# dub_siren_board.net
KiCad netlist of a schematic drawn in EasyEDA Pro
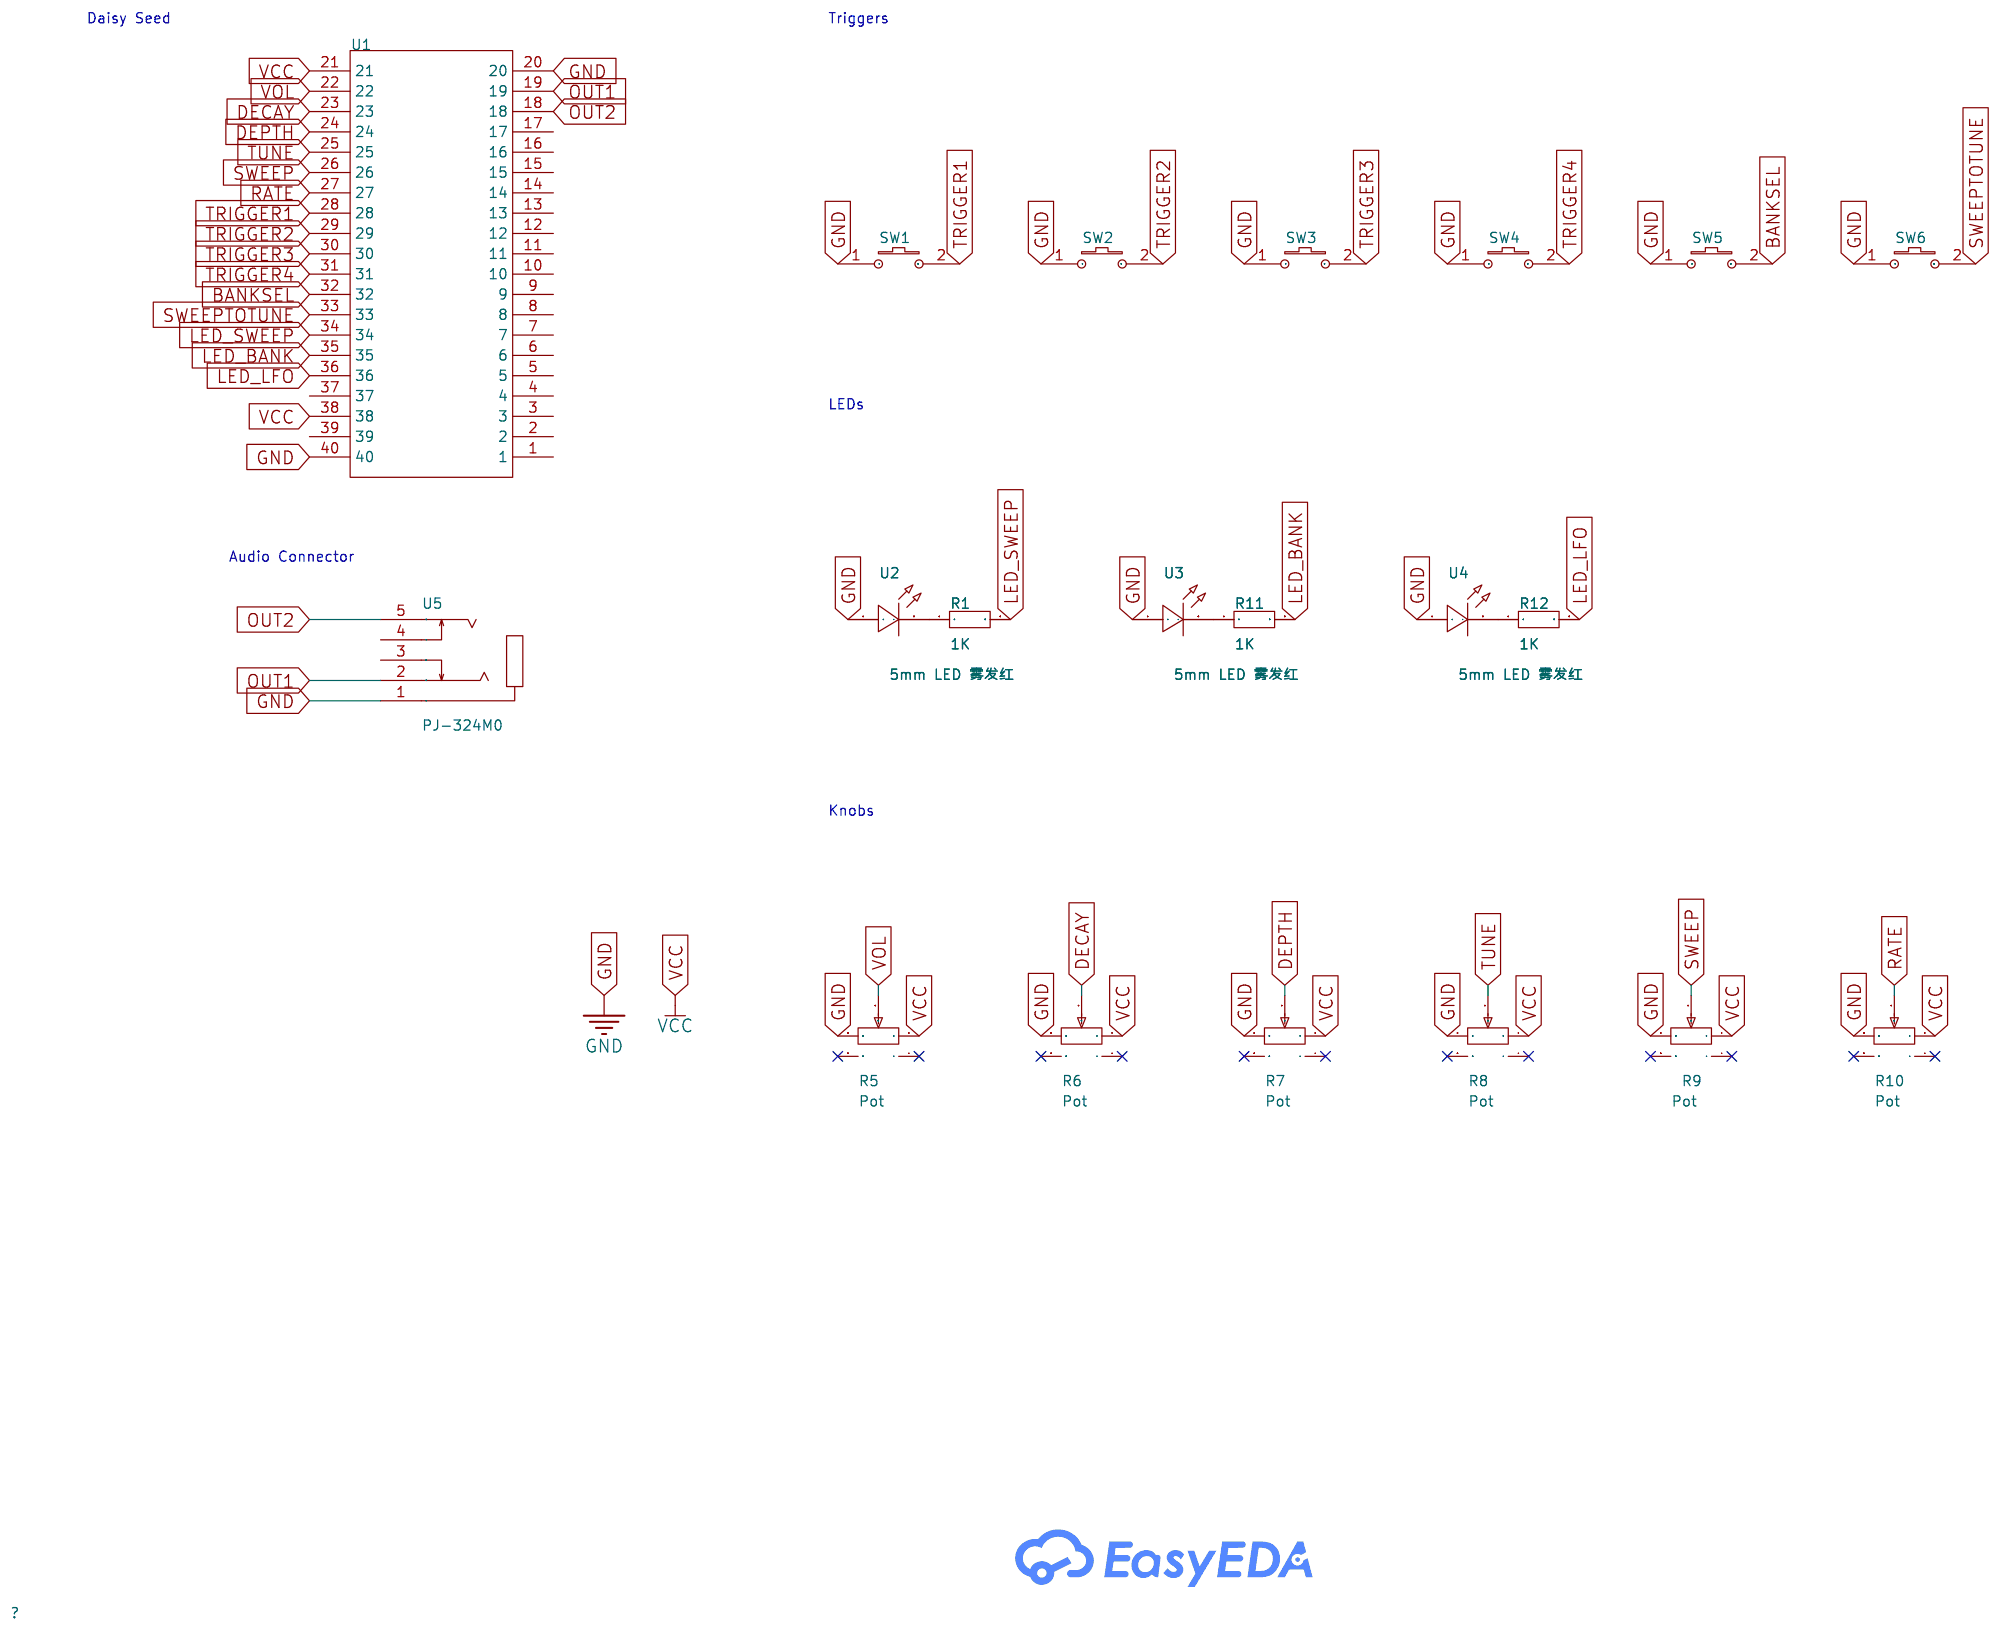
[diagram p0: schematic sheet]

(export (version "E")
  (design (tool "Eeschema 10.0.6"))
  (components
    (comp (ref "R1") (value "1K") (footprint "easyedapro:R0603") (libsource (lib "easyedapro") (part "Res")))
    (comp (ref "R5")
      (value "Pot")
      (footprint "easyedapro:RES-ADJ-TH_RV09")
      (libsource (lib "easyedapro") (part "RV09AF-40-15K-B10K-0C"))
    )
    (comp (ref "R6")
      (value "Pot")
      (footprint "easyedapro:RES-ADJ-TH_RV09")
      (libsource (lib "easyedapro") (part "RV09AF-40-15K-B10K-0C"))
    )
    (comp (ref "R7")
      (value "Pot")
      (footprint "easyedapro:RES-ADJ-TH_RV09")
      (libsource (lib "easyedapro") (part "RV09AF-40-15K-B10K-0C"))
    )
    (comp (ref "R8")
      (value "Pot")
      (footprint "easyedapro:RES-ADJ-TH_RV09")
      (libsource (lib "easyedapro") (part "RV09AF-40-15K-B10K-0C"))
    )
    (comp (ref "R9")
      (value "Pot")
      (footprint "easyedapro:RES-ADJ-TH_RV09")
      (libsource (lib "easyedapro") (part "RV09AF-40-15K-B10K-0C"))
    )
    (comp (ref "R10")
      (value "Pot")
      (footprint "easyedapro:RES-ADJ-TH_RV09")
      (libsource (lib "easyedapro") (part "RV09AF-40-15K-B10K-0C"))
    )
    (comp (ref "R11") (value "1K") (footprint "easyedapro:R0603") (libsource (lib "easyedapro") (part "Res")))
    (comp (ref "R12") (value "1K") (footprint "easyedapro:R0603") (libsource (lib "easyedapro") (part "Res")))
    (comp (ref "SW1")
      (value "~")
      (footprint "easyedapro:SWITCH CHERRY MX")
      (fields (field (name "Manufacturer Part") "MX1A-11NW") (field (name "Manufacturer") "ZF"))
      (libsource (lib "easyedapro") (part "Switch Cherry MX"))
    )
    (comp (ref "SW2")
      (value "~")
      (footprint "easyedapro:SWITCH CHERRY MX")
      (fields (field (name "Manufacturer Part") "MX1A-11NW") (field (name "Manufacturer") "ZF"))
      (libsource (lib "easyedapro") (part "Switch Cherry MX"))
    )
    (comp (ref "SW3")
      (value "~")
      (footprint "easyedapro:SWITCH CHERRY MX")
      (fields (field (name "Manufacturer Part") "MX1A-11NW") (field (name "Manufacturer") "ZF"))
      (libsource (lib "easyedapro") (part "Switch Cherry MX"))
    )
    (comp (ref "SW4")
      (value "~")
      (footprint "easyedapro:SWITCH CHERRY MX")
      (fields (field (name "Manufacturer Part") "MX1A-11NW") (field (name "Manufacturer") "ZF"))
      (libsource (lib "easyedapro") (part "Switch Cherry MX"))
    )
    (comp (ref "SW5")
      (value "~")
      (footprint "easyedapro:SWITCH CHERRY MX")
      (fields (field (name "Manufacturer Part") "MX1A-11NW") (field (name "Manufacturer") "ZF"))
      (libsource (lib "easyedapro") (part "Switch Cherry MX"))
    )
    (comp (ref "SW6")
      (value "~")
      (footprint "easyedapro:SWITCH CHERRY MX")
      (fields (field (name "Manufacturer Part") "MX1A-11NW") (field (name "Manufacturer") "ZF"))
      (libsource (lib "easyedapro") (part "Switch Cherry MX"))
    )
    (comp (ref "U1")
      (value "~")
      (footprint "easyedapro:40 PinSocket")
      (libsource (lib "easyedapro") (part "40 PinSocket"))
    )
    (comp (ref "U2")
      (value "5mm LED 雾发红")
      (footprint "easyedapro:LED-TH_BD5.0-P2.54-FD")
      (libsource (lib "easyedapro") (part "5MM LED 雾发红"))
    )
    (comp (ref "U3")
      (value "5mm LED 雾发红")
      (footprint "easyedapro:LED-TH_BD5.0-P2.54-FD")
      (libsource (lib "easyedapro") (part "5MM LED 雾发红"))
    )
    (comp (ref "U4")
      (value "5mm LED 雾发红")
      (footprint "easyedapro:LED-TH_BD5.0-P2.54-FD")
      (libsource (lib "easyedapro") (part "5MM LED 雾发红"))
    )
    (comp (ref "U5")
      (value "PJ-324M0")
      (footprint "easyedapro:AUDIO-TH_PJ-324-M")
      (fields (field (name "Manufacturer") "XKB Connection(中国星坤)"))
      (libsource (lib "easyedapro") (part "PJ-324M0"))
    )
  )
  (nets
    (net (code "1") (name "BANKSEL") (class "Default")
      (node (ref "SW5") (pin "2") (pinfunction "2_2") (pintype "input"))
      (node (ref "U1") (pin "32") (pinfunction "32_32") (pintype "input"))
    )
    (net (code "2") (name "DECAY") (class "Default")
      (node (ref "R6") (pin "2") (pinfunction "2_2") (pintype "input"))
      (node (ref "U1") (pin "23") (pinfunction "23_23") (pintype "input"))
    )
    (net (code "3") (name "DEPTH") (class "Default")
      (node (ref "R7") (pin "2") (pinfunction "2_2") (pintype "input"))
      (node (ref "U1") (pin "24") (pinfunction "24_24") (pintype "input"))
    )
    (net (code "4") (name "GND") (class "Default")
      (node (ref "R10") (pin "3") (pinfunction "3_3") (pintype "input"))
      (node (ref "R5") (pin "3") (pinfunction "3_3") (pintype "input"))
      (node (ref "R6") (pin "3") (pinfunction "3_3") (pintype "input"))
      (node (ref "R7") (pin "3") (pinfunction "3_3") (pintype "input"))
      (node (ref "R8") (pin "3") (pinfunction "3_3") (pintype "input"))
      (node (ref "R9") (pin "3") (pinfunction "3_3") (pintype "input"))
      (node (ref "SW1") (pin "1") (pinfunction "1_1") (pintype "input"))
      (node (ref "SW2") (pin "1") (pinfunction "1_1") (pintype "input"))
      (node (ref "SW3") (pin "1") (pinfunction "1_1") (pintype "input"))
      (node (ref "SW4") (pin "1") (pinfunction "1_1") (pintype "input"))
      (node (ref "SW5") (pin "1") (pinfunction "1_1") (pintype "input"))
      (node (ref "SW6") (pin "1") (pinfunction "1_1") (pintype "input"))
      (node (ref "U1") (pin "20") (pinfunction "20_20") (pintype "input"))
      (node (ref "U1") (pin "40") (pinfunction "40_40") (pintype "input"))
      (node (ref "U2") (pin "1") (pinfunction "+_1") (pintype "unspecified"))
      (node (ref "U3") (pin "1") (pinfunction "+_1") (pintype "unspecified"))
      (node (ref "U4") (pin "1") (pinfunction "+_1") (pintype "unspecified"))
      (node (ref "U5") (pin "1") (pinfunction "1_1") (pintype "unspecified"))
    )
    (net (code "5") (name "LED_BANK") (class "Default")
      (node (ref "R11") (pin "2") (pinfunction "2_2") (pintype "input"))
      (node (ref "U1") (pin "35") (pinfunction "35_35") (pintype "input"))
    )
    (net (code "6") (name "LED_LFO") (class "Default")
      (node (ref "R12") (pin "2") (pinfunction "2_2") (pintype "input"))
      (node (ref "U1") (pin "36") (pinfunction "36_36") (pintype "input"))
    )
    (net (code "7") (name "LED_SWEEP") (class "Default")
      (node (ref "R1") (pin "2") (pinfunction "2_2") (pintype "input"))
      (node (ref "U1") (pin "34") (pinfunction "34_34") (pintype "input"))
    )
    (net (code "8") (name "Net-(U2--)") (class "Default")
      (node (ref "R1") (pin "1") (pinfunction "1_1") (pintype "input"))
      (node (ref "U2") (pin "2") (pinfunction "-_2") (pintype "unspecified"))
    )
    (net (code "9") (name "Net-(U3--)") (class "Default")
      (node (ref "R11") (pin "1") (pinfunction "1_1") (pintype "input"))
      (node (ref "U3") (pin "2") (pinfunction "-_2") (pintype "unspecified"))
    )
    (net (code "10") (name "Net-(U4--)") (class "Default")
      (node (ref "R12") (pin "1") (pinfunction "1_1") (pintype "input"))
      (node (ref "U4") (pin "2") (pinfunction "-_2") (pintype "unspecified"))
    )
    (net (code "11") (name "OUT1") (class "Default")
      (node (ref "U1") (pin "19") (pinfunction "19_19") (pintype "input"))
      (node (ref "U5") (pin "2") (pinfunction "2_2") (pintype "unspecified"))
    )
    (net (code "12") (name "OUT2") (class "Default")
      (node (ref "U1") (pin "18") (pinfunction "18_18") (pintype "input"))
      (node (ref "U5") (pin "5") (pinfunction "5_5") (pintype "unspecified"))
    )
    (net (code "13") (name "RATE") (class "Default")
      (node (ref "R10") (pin "2") (pinfunction "2_2") (pintype "input"))
      (node (ref "U1") (pin "27") (pinfunction "27_27") (pintype "input"))
    )
    (net (code "14") (name "SWEEP") (class "Default")
      (node (ref "R9") (pin "2") (pinfunction "2_2") (pintype "input"))
      (node (ref "U1") (pin "26") (pinfunction "26_26") (pintype "input"))
    )
    (net (code "15") (name "SWEEPTOTUNE") (class "Default")
      (node (ref "SW6") (pin "2") (pinfunction "2_2") (pintype "input"))
      (node (ref "U1") (pin "33") (pinfunction "33_33") (pintype "input"))
    )
    (net (code "16") (name "TRIGGER1") (class "Default")
      (node (ref "SW1") (pin "2") (pinfunction "2_2") (pintype "input"))
      (node (ref "U1") (pin "28") (pinfunction "28_28") (pintype "input"))
    )
    (net (code "17") (name "TRIGGER2") (class "Default")
      (node (ref "SW2") (pin "2") (pinfunction "2_2") (pintype "input"))
      (node (ref "U1") (pin "29") (pinfunction "29_29") (pintype "input"))
    )
    (net (code "18") (name "TRIGGER3") (class "Default")
      (node (ref "SW3") (pin "2") (pinfunction "2_2") (pintype "input"))
      (node (ref "U1") (pin "30") (pinfunction "30_30") (pintype "input"))
    )
    (net (code "19") (name "TRIGGER4") (class "Default")
      (node (ref "SW4") (pin "2") (pinfunction "2_2") (pintype "input"))
      (node (ref "U1") (pin "31") (pinfunction "31_31") (pintype "input"))
    )
    (net (code "20") (name "TUNE") (class "Default")
      (node (ref "R8") (pin "2") (pinfunction "2_2") (pintype "input"))
      (node (ref "U1") (pin "25") (pinfunction "25_25") (pintype "input"))
    )
    (net (code "21") (name "VCC") (class "Default")
      (node (ref "R10") (pin "1") (pinfunction "1_1") (pintype "input"))
      (node (ref "R5") (pin "1") (pinfunction "1_1") (pintype "input"))
      (node (ref "R6") (pin "1") (pinfunction "1_1") (pintype "input"))
      (node (ref "R7") (pin "1") (pinfunction "1_1") (pintype "input"))
      (node (ref "R8") (pin "1") (pinfunction "1_1") (pintype "input"))
      (node (ref "R9") (pin "1") (pinfunction "1_1") (pintype "input"))
      (node (ref "U1") (pin "21") (pinfunction "21_21") (pintype "input"))
      (node (ref "U1") (pin "38") (pinfunction "38_38") (pintype "input"))
    )
    (net (code "22") (name "VOL") (class "Default")
      (node (ref "R5") (pin "2") (pinfunction "2_2") (pintype "input"))
      (node (ref "U1") (pin "22") (pinfunction "22_22") (pintype "input"))
    )
    (net (code "23") (name "unconnected-(R5-Pad4)") (class "Default")
      (node (ref "R5") (pin "4") (pinfunction "4_4") (pintype "input+no_connect"))
    )
    (net (code "24") (name "unconnected-(R5-Pad5)") (class "Default")
      (node (ref "R5") (pin "5") (pinfunction "5_5") (pintype "input+no_connect"))
    )
    (net (code "25") (name "unconnected-(R6-Pad4)") (class "Default")
      (node (ref "R6") (pin "4") (pinfunction "4_4") (pintype "input+no_connect"))
    )
    (net (code "26") (name "unconnected-(R6-Pad5)") (class "Default")
      (node (ref "R6") (pin "5") (pinfunction "5_5") (pintype "input+no_connect"))
    )
    (net (code "27") (name "unconnected-(R7-Pad4)") (class "Default")
      (node (ref "R7") (pin "4") (pinfunction "4_4") (pintype "input+no_connect"))
    )
    (net (code "28") (name "unconnected-(R7-Pad5)") (class "Default")
      (node (ref "R7") (pin "5") (pinfunction "5_5") (pintype "input+no_connect"))
    )
    (net (code "29") (name "unconnected-(R8-Pad4)") (class "Default")
      (node (ref "R8") (pin "4") (pinfunction "4_4") (pintype "input+no_connect"))
    )
    (net (code "30") (name "unconnected-(R8-Pad5)") (class "Default")
      (node (ref "R8") (pin "5") (pinfunction "5_5") (pintype "input+no_connect"))
    )
    (net (code "31") (name "unconnected-(R9-Pad4)") (class "Default")
      (node (ref "R9") (pin "4") (pinfunction "4_4") (pintype "input+no_connect"))
    )
    (net (code "32") (name "unconnected-(R9-Pad5)") (class "Default")
      (node (ref "R9") (pin "5") (pinfunction "5_5") (pintype "input+no_connect"))
    )
    (net (code "33") (name "unconnected-(R10-Pad4)") (class "Default")
      (node (ref "R10") (pin "4") (pinfunction "4_4") (pintype "input+no_connect"))
    )
    (net (code "34") (name "unconnected-(R10-Pad5)") (class "Default")
      (node (ref "R10") (pin "5") (pinfunction "5_5") (pintype "input+no_connect"))
    )
    (net (code "35") (name "unconnected-(U1-Pad1)") (class "Default")
      (node (ref "U1") (pin "1") (pinfunction "1_1") (pintype "input"))
    )
    (net (code "36") (name "unconnected-(U1-Pad2)") (class "Default")
      (node (ref "U1") (pin "2") (pinfunction "2_2") (pintype "input"))
    )
    (net (code "37") (name "unconnected-(U1-Pad3)") (class "Default")
      (node (ref "U1") (pin "3") (pinfunction "3_3") (pintype "input"))
    )
    (net (code "38") (name "unconnected-(U1-Pad4)") (class "Default")
      (node (ref "U1") (pin "4") (pinfunction "4_4") (pintype "input"))
    )
    (net (code "39") (name "unconnected-(U1-Pad5)") (class "Default")
      (node (ref "U1") (pin "5") (pinfunction "5_5") (pintype "input"))
    )
    (net (code "40") (name "unconnected-(U1-Pad6)") (class "Default")
      (node (ref "U1") (pin "6") (pinfunction "6_6") (pintype "input"))
    )
    (net (code "41") (name "unconnected-(U1-Pad7)") (class "Default")
      (node (ref "U1") (pin "7") (pinfunction "7_7") (pintype "input"))
    )
    (net (code "42") (name "unconnected-(U1-Pad8)") (class "Default")
      (node (ref "U1") (pin "8") (pinfunction "8_8") (pintype "input"))
    )
    (net (code "43") (name "unconnected-(U1-Pad9)") (class "Default")
      (node (ref "U1") (pin "9") (pinfunction "9_9") (pintype "input"))
    )
    (net (code "44") (name "unconnected-(U1-Pad10)") (class "Default")
      (node (ref "U1") (pin "10") (pinfunction "10_10") (pintype "input"))
    )
    (net (code "45") (name "unconnected-(U1-Pad11)") (class "Default")
      (node (ref "U1") (pin "11") (pinfunction "11_11") (pintype "input"))
    )
    (net (code "46") (name "unconnected-(U1-Pad12)") (class "Default")
      (node (ref "U1") (pin "12") (pinfunction "12_12") (pintype "input"))
    )
    (net (code "47") (name "unconnected-(U1-Pad13)") (class "Default")
      (node (ref "U1") (pin "13") (pinfunction "13_13") (pintype "input"))
    )
    (net (code "48") (name "unconnected-(U1-Pad14)") (class "Default")
      (node (ref "U1") (pin "14") (pinfunction "14_14") (pintype "input"))
    )
    (net (code "49") (name "unconnected-(U1-Pad15)") (class "Default")
      (node (ref "U1") (pin "15") (pinfunction "15_15") (pintype "input"))
    )
    (net (code "50") (name "unconnected-(U1-Pad16)") (class "Default")
      (node (ref "U1") (pin "16") (pinfunction "16_16") (pintype "input"))
    )
    (net (code "51") (name "unconnected-(U1-Pad17)") (class "Default")
      (node (ref "U1") (pin "17") (pinfunction "17_17") (pintype "input"))
    )
    (net (code "52") (name "unconnected-(U1-Pad37)") (class "Default")
      (node (ref "U1") (pin "37") (pinfunction "37_37") (pintype "input"))
    )
    (net (code "53") (name "unconnected-(U1-Pad39)") (class "Default")
      (node (ref "U1") (pin "39") (pinfunction "39_39") (pintype "input"))
    )
    (net (code "54") (name "unconnected-(U5-Pad3)") (class "Default")
      (node (ref "U5") (pin "3") (pinfunction "3_3") (pintype "unspecified"))
    )
    (net (code "55") (name "unconnected-(U5-Pad4)") (class "Default")
      (node (ref "U5") (pin "4") (pinfunction "4_4") (pintype "unspecified"))
    )
  )
)
